# atlas_double.net
KiCad netlist of a schematic drawn in EAGLE
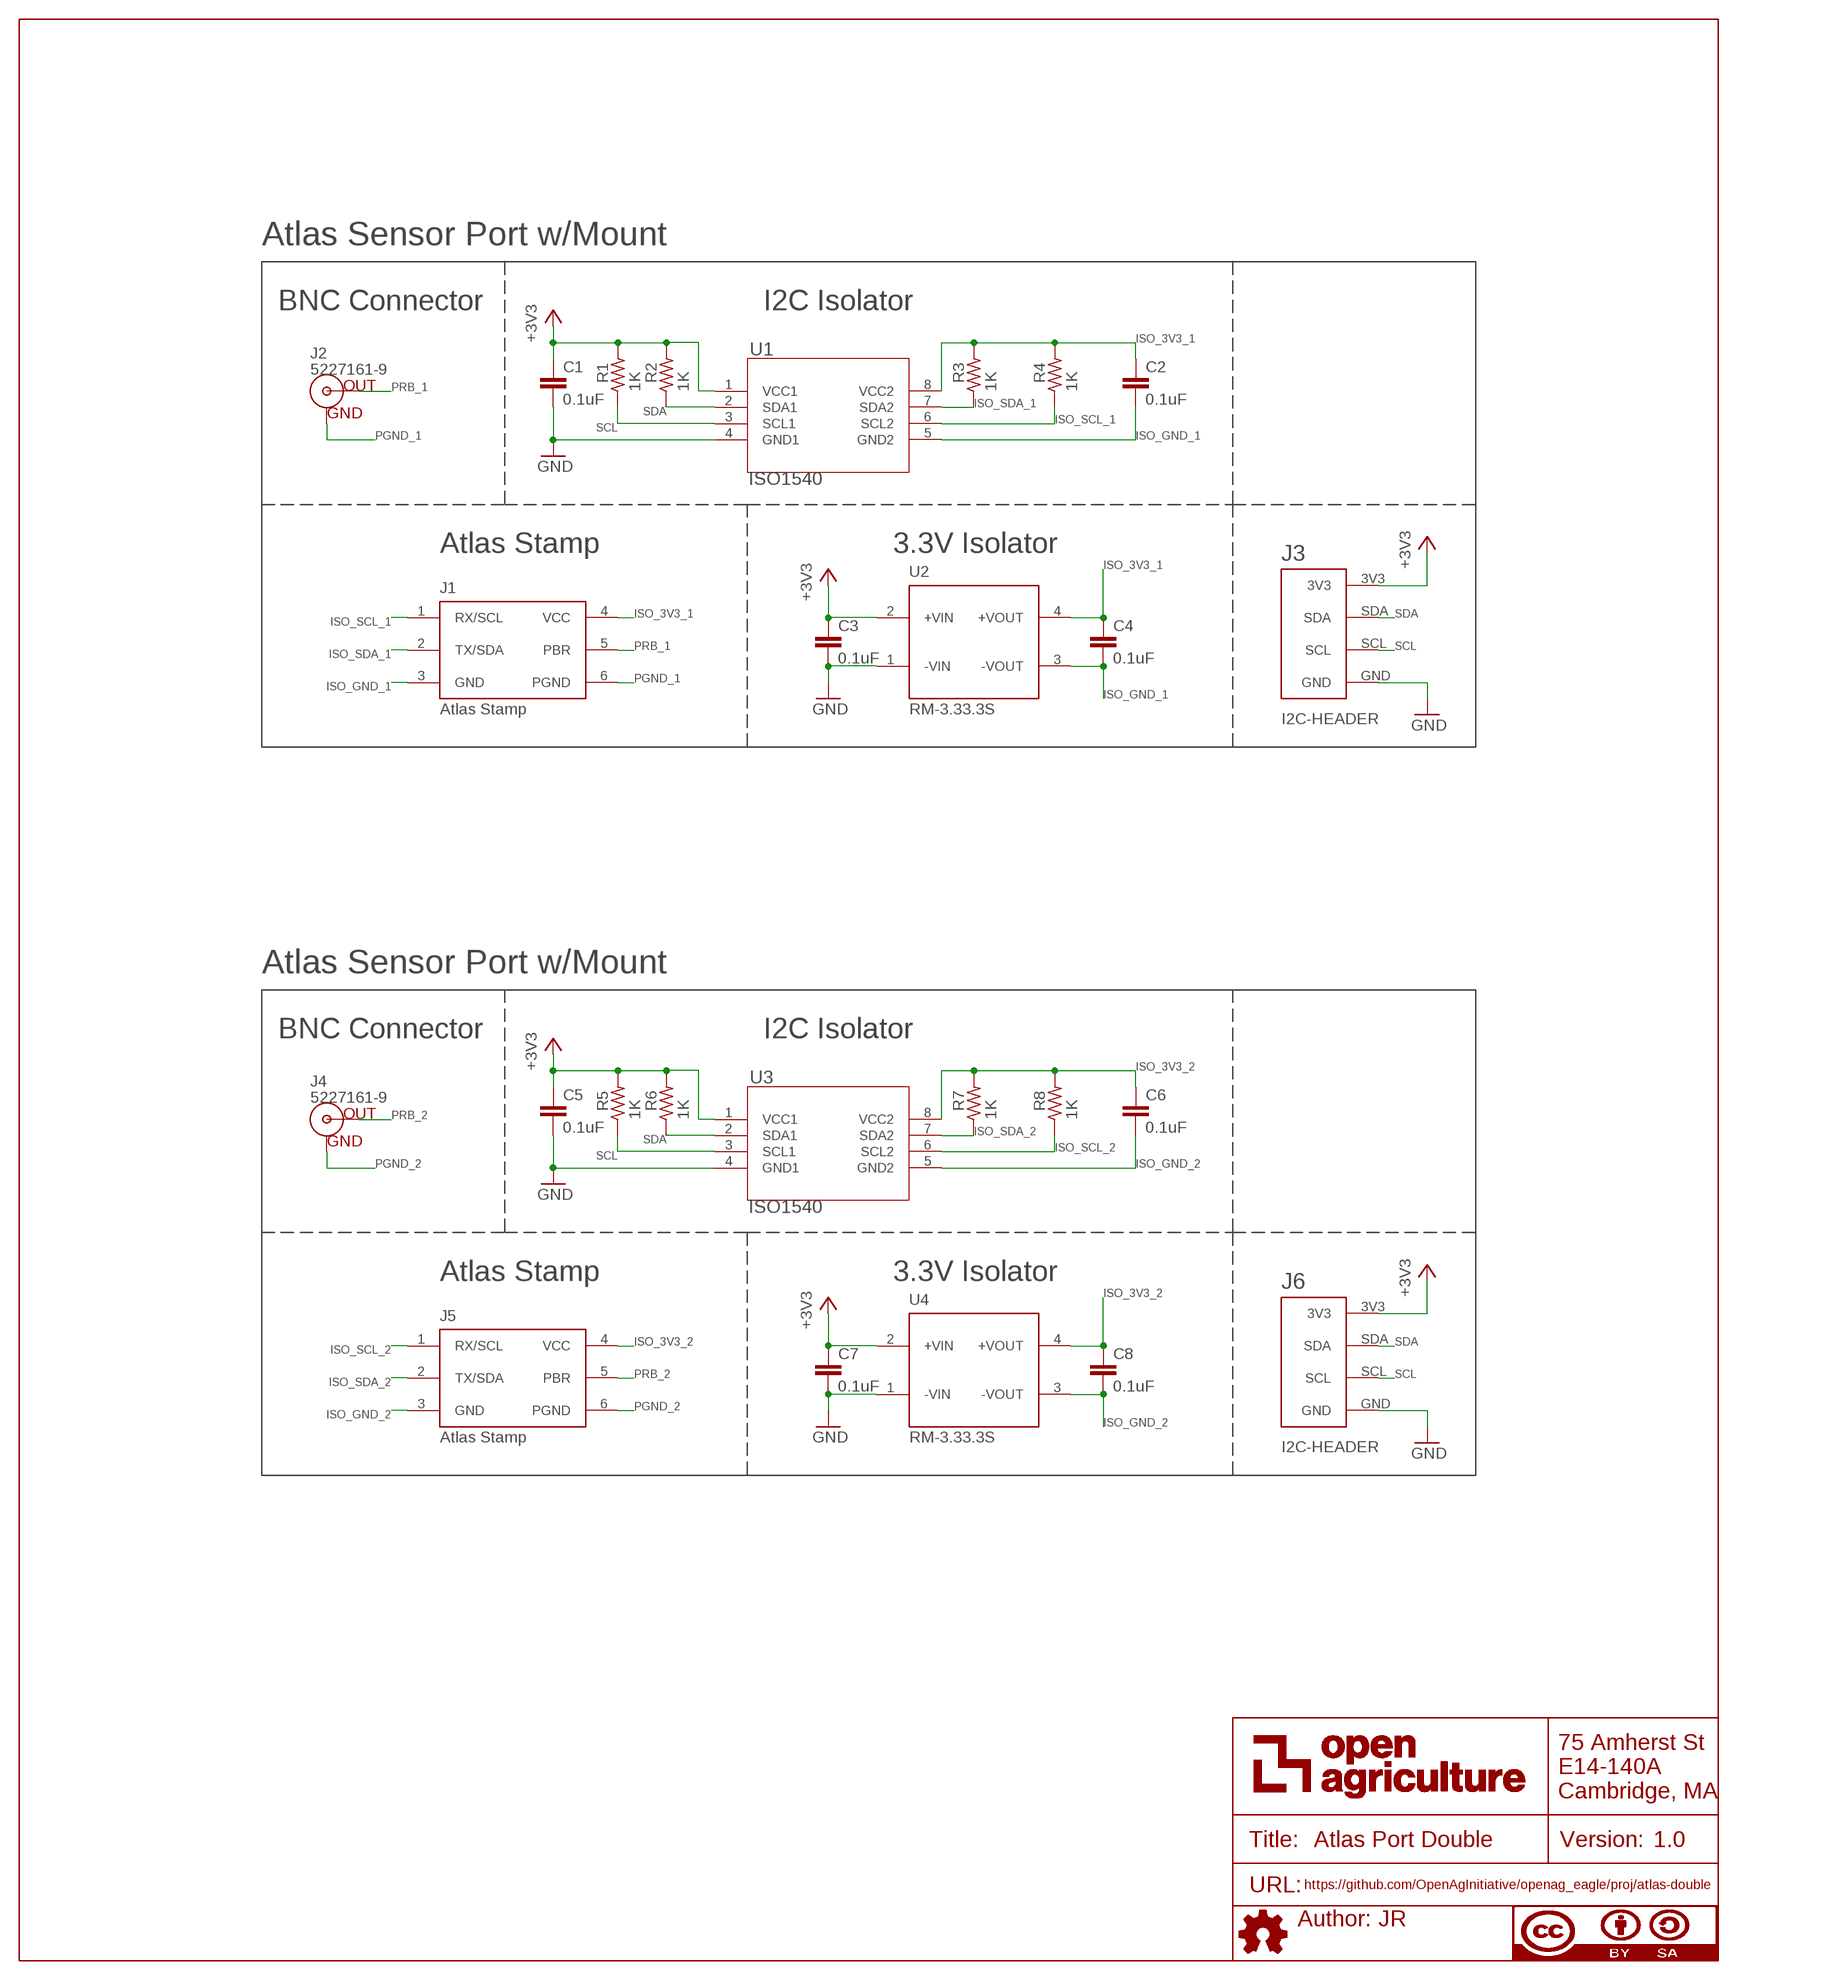
[diagram p0: schematic, sheet 1]

(export (version "E")
  (design (tool "Eeschema 10.0.6"))
  (components
    (comp (ref "C1")
      (value "0.1uF")
      (footprint "eagle-import:C0603")
      (libsource (lib "eagle-import") (part "0.1UF-C0603C104K5RACTU"))
    )
    (comp (ref "C2")
      (value "0.1uF")
      (footprint "eagle-import:C0603")
      (libsource (lib "eagle-import") (part "0.1UF-C0603C104K5RACTU"))
    )
    (comp (ref "C3")
      (value "0.1uF")
      (footprint "eagle-import:C0603")
      (libsource (lib "eagle-import") (part "0.1UF-C0603C104K5RACTU"))
    )
    (comp (ref "C4")
      (value "0.1uF")
      (footprint "eagle-import:C0603")
      (libsource (lib "eagle-import") (part "0.1UF-C0603C104K5RACTU"))
    )
    (comp (ref "C5")
      (value "0.1uF")
      (footprint "eagle-import:C0603")
      (libsource (lib "eagle-import") (part "0.1UF-C0603C104K5RACTU"))
    )
    (comp (ref "C6")
      (value "0.1uF")
      (footprint "eagle-import:C0603")
      (libsource (lib "eagle-import") (part "0.1UF-C0603C104K5RACTU"))
    )
    (comp (ref "C7")
      (value "0.1uF")
      (footprint "eagle-import:C0603")
      (libsource (lib "eagle-import") (part "0.1UF-C0603C104K5RACTU"))
    )
    (comp (ref "C8")
      (value "0.1uF")
      (footprint "eagle-import:C0603")
      (libsource (lib "eagle-import") (part "0.1UF-C0603C104K5RACTU"))
    )
    (comp (ref "FRAME1")
      (value "DOCFIELD")
      (footprint "eagle-import:DOCFIELD")
      (fields
        (field (name "TITLE") "Example Template")
        (field (name "AUTHOR") "XX")
        (field (name "VER") "1.0")
        (field (name "URL") "https://github.com/OpenAgInitiative/openag_eagle_template")
        (field (name "AUTHOR_1") "JR")
        (field (name "TITLE_1") "Atlas Port Double")
        (field (name "URL_1") "https://github.com/OpenAgInitiative/openag_eagle/proj/atlas-double")
      )
      (libsource (lib "eagle-import") (part "DOCFIELD"))
    )
    (comp (ref "J1")
      (value "Atlas Stamp")
      (footprint "eagle-import:ATLAS-STAMP")
      (libsource (lib "eagle-import") (part "ATLAS-STAMP"))
    )
    (comp (ref "J2")
      (value "5227161-9")
      (footprint "eagle-import:BNC")
      (libsource (lib "eagle-import") (part "BNC-5227161-9PTH"))
    )
    (comp (ref "J3")
      (value "I2C-HEADER")
      (footprint "eagle-import:OPENAG-I2C-HEADER")
      (libsource (lib "eagle-import") (part "OPENAG-I2C-HEADER"))
    )
    (comp (ref "J4")
      (value "5227161-9")
      (footprint "eagle-import:BNC")
      (libsource (lib "eagle-import") (part "BNC-5227161-9PTH"))
    )
    (comp (ref "J5")
      (value "Atlas Stamp")
      (footprint "eagle-import:ATLAS-STAMP")
      (libsource (lib "eagle-import") (part "ATLAS-STAMP"))
    )
    (comp (ref "J6")
      (value "I2C-HEADER")
      (footprint "eagle-import:OPENAG-I2C-HEADER")
      (libsource (lib "eagle-import") (part "OPENAG-I2C-HEADER"))
    )
    (comp (ref "R1")
      (value "1K")
      (footprint "eagle-import:RC0603N")
      (libsource (lib "eagle-import") (part "1K-ERJ-PB3D1001V"))
    )
    (comp (ref "R2")
      (value "1K")
      (footprint "eagle-import:RC0603N")
      (libsource (lib "eagle-import") (part "1K-ERJ-PB3D1001V"))
    )
    (comp (ref "R3")
      (value "1K")
      (footprint "eagle-import:RC0603N")
      (libsource (lib "eagle-import") (part "1K-ERJ-PB3D1001V"))
    )
    (comp (ref "R4")
      (value "1K")
      (footprint "eagle-import:RC0603N")
      (libsource (lib "eagle-import") (part "1K-ERJ-PB3D1001V"))
    )
    (comp (ref "R5")
      (value "1K")
      (footprint "eagle-import:RC0603N")
      (libsource (lib "eagle-import") (part "1K-ERJ-PB3D1001V"))
    )
    (comp (ref "R6")
      (value "1K")
      (footprint "eagle-import:RC0603N")
      (libsource (lib "eagle-import") (part "1K-ERJ-PB3D1001V"))
    )
    (comp (ref "R7")
      (value "1K")
      (footprint "eagle-import:RC0603N")
      (libsource (lib "eagle-import") (part "1K-ERJ-PB3D1001V"))
    )
    (comp (ref "R8")
      (value "1K")
      (footprint "eagle-import:RC0603N")
      (libsource (lib "eagle-import") (part "1K-ERJ-PB3D1001V"))
    )
    (comp (ref "U1")
      (value "ISO1540")
      (footprint "eagle-import:D8")
      (fields (field (name "MF") "Texas Instruments") (field (name "MPN") "ISO1540DR"))
      (libsource (lib "eagle-import") (part "ISO1540DR"))
    )
    (comp (ref "U2")
      (value "RM-3.33.3S")
      (footprint "eagle-import:SIP4")
      (libsource (lib "eagle-import") (part "RM3.33.3S"))
    )
    (comp (ref "U3")
      (value "ISO1540")
      (footprint "eagle-import:D8")
      (fields (field (name "MF") "Texas Instruments") (field (name "MPN") "ISO1540DR"))
      (libsource (lib "eagle-import") (part "ISO1540DR"))
    )
    (comp (ref "U4")
      (value "RM-3.33.3S")
      (footprint "eagle-import:SIP4")
      (libsource (lib "eagle-import") (part "RM3.33.3S"))
    )
  )
  (nets
    (net (code "1") (name "+3V3") (class "Default")
      (node (ref "C1") (pin "1") (pinfunction "1_1") (pintype "passive"))
      (node (ref "C3") (pin "1") (pinfunction "1_1") (pintype "passive"))
      (node (ref "C5") (pin "1") (pinfunction "1_1") (pintype "passive"))
      (node (ref "C7") (pin "1") (pinfunction "1_1") (pintype "passive"))
      (node (ref "J3") (pin "3V3") (pinfunction "3V3_3V3") (pintype "bidirectional"))
      (node (ref "J6") (pin "3V3") (pinfunction "3V3_3V3") (pintype "bidirectional"))
      (node (ref "R1") (pin "2") (pinfunction "2_2") (pintype "passive"))
      (node (ref "R2") (pin "2") (pinfunction "2_2") (pintype "passive"))
      (node (ref "R5") (pin "2") (pinfunction "2_2") (pintype "passive"))
      (node (ref "R6") (pin "2") (pinfunction "2_2") (pintype "passive"))
      (node (ref "U1") (pin "1") (pinfunction "VCC1_1") (pintype "power_in"))
      (node (ref "U2") (pin "2") (pinfunction "+VIN_2") (pintype "power_in"))
      (node (ref "U3") (pin "1") (pinfunction "VCC1_1") (pintype "power_in"))
      (node (ref "U4") (pin "2") (pinfunction "+VIN_2") (pintype "power_in"))
    )
    (net (code "2") (name "GND") (class "Default")
      (node (ref "C1") (pin "2") (pinfunction "2_2") (pintype "passive"))
      (node (ref "C3") (pin "2") (pinfunction "2_2") (pintype "passive"))
      (node (ref "C5") (pin "2") (pinfunction "2_2") (pintype "passive"))
      (node (ref "C7") (pin "2") (pinfunction "2_2") (pintype "passive"))
      (node (ref "J3") (pin "GND") (pinfunction "GND_GND") (pintype "bidirectional"))
      (node (ref "J6") (pin "GND") (pinfunction "GND_GND") (pintype "bidirectional"))
      (node (ref "U1") (pin "4") (pinfunction "GND1_4") (pintype "power_in"))
      (node (ref "U2") (pin "1") (pinfunction "-VIN_1") (pintype "power_in"))
      (node (ref "U3") (pin "4") (pinfunction "GND1_4") (pintype "power_in"))
      (node (ref "U4") (pin "1") (pinfunction "-VIN_1") (pintype "power_in"))
    )
    (net (code "3") (name "ISO_3V3_1") (class "Default")
      (node (ref "C2") (pin "1") (pinfunction "1_1") (pintype "passive"))
      (node (ref "C4") (pin "1") (pinfunction "1_1") (pintype "passive"))
      (node (ref "J1") (pin "4") (pinfunction "VCC_4") (pintype "power_in"))
      (node (ref "R3") (pin "2") (pinfunction "2_2") (pintype "passive"))
      (node (ref "R4") (pin "2") (pinfunction "2_2") (pintype "passive"))
      (node (ref "U1") (pin "8") (pinfunction "VCC2_8") (pintype "power_in"))
      (node (ref "U2") (pin "4") (pinfunction "+VOUT_4") (pintype "power_in"))
    )
    (net (code "4") (name "ISO_3V3_2") (class "Default")
      (node (ref "C6") (pin "1") (pinfunction "1_1") (pintype "passive"))
      (node (ref "C8") (pin "1") (pinfunction "1_1") (pintype "passive"))
      (node (ref "J5") (pin "4") (pinfunction "VCC_4") (pintype "power_in"))
      (node (ref "R7") (pin "2") (pinfunction "2_2") (pintype "passive"))
      (node (ref "R8") (pin "2") (pinfunction "2_2") (pintype "passive"))
      (node (ref "U3") (pin "8") (pinfunction "VCC2_8") (pintype "power_in"))
      (node (ref "U4") (pin "4") (pinfunction "+VOUT_4") (pintype "power_in"))
    )
    (net (code "5") (name "ISO_GND_1") (class "Default")
      (node (ref "C2") (pin "2") (pinfunction "2_2") (pintype "passive"))
      (node (ref "C4") (pin "2") (pinfunction "2_2") (pintype "passive"))
      (node (ref "J1") (pin "3") (pinfunction "GND_3") (pintype "power_in"))
      (node (ref "U1") (pin "5") (pinfunction "GND2_5") (pintype "power_in"))
      (node (ref "U2") (pin "3") (pinfunction "-VOUT_3") (pintype "power_in"))
    )
    (net (code "6") (name "ISO_GND_2") (class "Default")
      (node (ref "C6") (pin "2") (pinfunction "2_2") (pintype "passive"))
      (node (ref "C8") (pin "2") (pinfunction "2_2") (pintype "passive"))
      (node (ref "J5") (pin "3") (pinfunction "GND_3") (pintype "power_in"))
      (node (ref "U3") (pin "5") (pinfunction "GND2_5") (pintype "power_in"))
      (node (ref "U4") (pin "3") (pinfunction "-VOUT_3") (pintype "power_in"))
    )
    (net (code "7") (name "ISO_SCL_1") (class "Default")
      (node (ref "J1") (pin "1") (pinfunction "RX/SCL_1") (pintype "bidirectional"))
      (node (ref "R4") (pin "1") (pinfunction "1_1") (pintype "passive"))
      (node (ref "U1") (pin "6") (pinfunction "SCL2_6") (pintype "bidirectional"))
    )
    (net (code "8") (name "ISO_SCL_2") (class "Default")
      (node (ref "J5") (pin "1") (pinfunction "RX/SCL_1") (pintype "bidirectional"))
      (node (ref "R8") (pin "1") (pinfunction "1_1") (pintype "passive"))
      (node (ref "U3") (pin "6") (pinfunction "SCL2_6") (pintype "bidirectional"))
    )
    (net (code "9") (name "ISO_SDA_1") (class "Default")
      (node (ref "J1") (pin "2") (pinfunction "TX/SDA_2") (pintype "bidirectional"))
      (node (ref "R3") (pin "1") (pinfunction "1_1") (pintype "passive"))
      (node (ref "U1") (pin "7") (pinfunction "SDA2_7") (pintype "bidirectional"))
    )
    (net (code "10") (name "ISO_SDA_2") (class "Default")
      (node (ref "J5") (pin "2") (pinfunction "TX/SDA_2") (pintype "bidirectional"))
      (node (ref "R7") (pin "1") (pinfunction "1_1") (pintype "passive"))
      (node (ref "U3") (pin "7") (pinfunction "SDA2_7") (pintype "bidirectional"))
    )
    (net (code "11") (name "PGND_1") (class "Default")
      (node (ref "J1") (pin "6") (pinfunction "PGND_6") (pintype "power_in"))
      (node (ref "J2") (pin "GND") (pinfunction "GND_GND") (pintype "bidirectional"))
    )
    (net (code "12") (name "PGND_2") (class "Default")
      (node (ref "J4") (pin "GND") (pinfunction "GND_GND") (pintype "bidirectional"))
      (node (ref "J5") (pin "6") (pinfunction "PGND_6") (pintype "power_in"))
    )
    (net (code "13") (name "PRB_1") (class "Default")
      (node (ref "J1") (pin "5") (pinfunction "PBR_5") (pintype "bidirectional"))
      (node (ref "J2") (pin "S") (pinfunction "OUT_S") (pintype "bidirectional"))
    )
    (net (code "14") (name "PRB_2") (class "Default")
      (node (ref "J4") (pin "S") (pinfunction "OUT_S") (pintype "bidirectional"))
      (node (ref "J5") (pin "5") (pinfunction "PBR_5") (pintype "bidirectional"))
    )
    (net (code "15") (name "SCL") (class "Default")
      (node (ref "J3") (pin "SCL") (pinfunction "SCL_SCL") (pintype "bidirectional"))
      (node (ref "J6") (pin "SCL") (pinfunction "SCL_SCL") (pintype "bidirectional"))
      (node (ref "R1") (pin "1") (pinfunction "1_1") (pintype "passive"))
      (node (ref "R5") (pin "1") (pinfunction "1_1") (pintype "passive"))
      (node (ref "U1") (pin "3") (pinfunction "SCL1_3") (pintype "bidirectional"))
      (node (ref "U3") (pin "3") (pinfunction "SCL1_3") (pintype "bidirectional"))
    )
    (net (code "16") (name "SDA") (class "Default")
      (node (ref "J3") (pin "SDA") (pinfunction "SDA_SDA") (pintype "bidirectional"))
      (node (ref "J6") (pin "SDA") (pinfunction "SDA_SDA") (pintype "bidirectional"))
      (node (ref "R2") (pin "1") (pinfunction "1_1") (pintype "passive"))
      (node (ref "R6") (pin "1") (pinfunction "1_1") (pintype "passive"))
      (node (ref "U1") (pin "2") (pinfunction "SDA1_2") (pintype "bidirectional"))
      (node (ref "U3") (pin "2") (pinfunction "SDA1_2") (pintype "bidirectional"))
    )
  )
)
